# Sheet1.net
KiCad netlist of a schematic drawn in Altium Designer
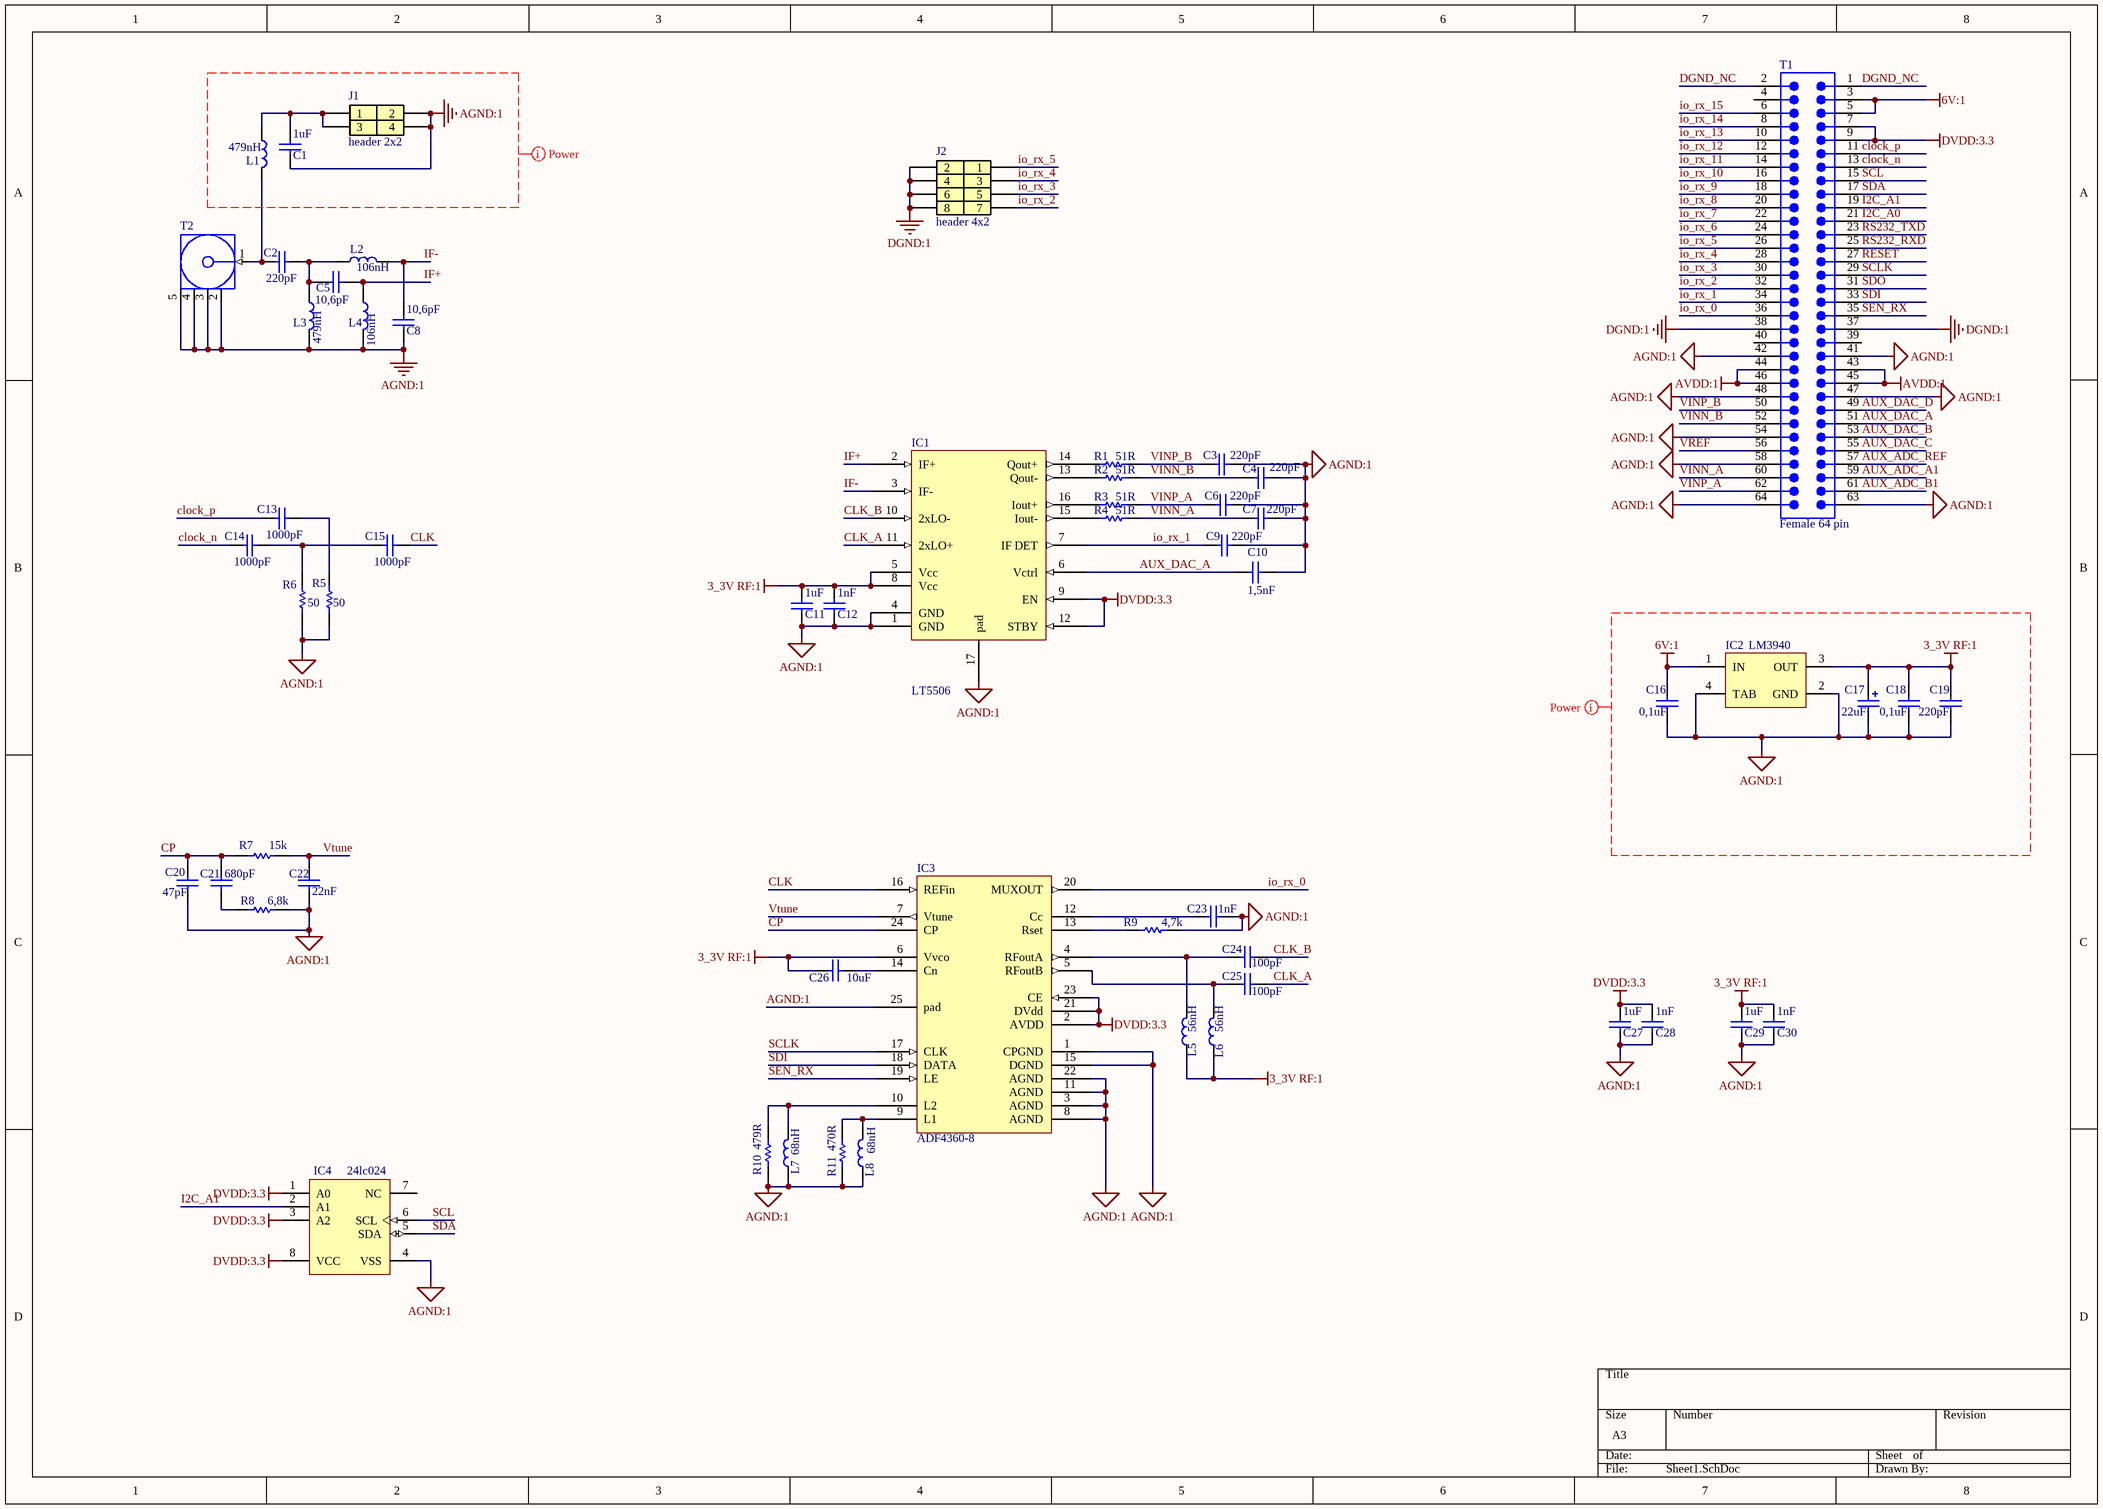
[diagram p0: Sheet1.SchDoc]

(export (version "E")
  (design (tool "Eeschema 10.0.6"))
  (components
    (comp (ref "C1") (value "1uF") (footprint "0805 cap") (libsource (lib "DB") (part "ceramic capacitor")))
    (comp (ref "C2") (value "220pF") (footprint "0805 cap") (libsource (lib "DB") (part "ceramic capacitor")))
    (comp (ref "C3") (value "220pF") (footprint "0805 cap") (libsource (lib "DB") (part "ceramic capacitor")))
    (comp (ref "C4") (value "220pF") (footprint "0805 cap") (libsource (lib "DB") (part "ceramic capacitor")))
    (comp (ref "C5")
      (value "10,6pF")
      (footprint "0805 cap")
      (libsource (lib "DB") (part "ceramic capacitor"))
    )
    (comp (ref "C6") (value "220pF") (footprint "0805 cap") (libsource (lib "DB") (part "ceramic capacitor")))
    (comp (ref "C7") (value "220pF") (footprint "0805 cap") (libsource (lib "DB") (part "ceramic capacitor")))
    (comp (ref "C8")
      (value "10,6pF")
      (footprint "0805 cap")
      (libsource (lib "DB") (part "ceramic capacitor"))
    )
    (comp (ref "C9") (value "220pF") (footprint "0805 cap") (libsource (lib "DB") (part "ceramic capacitor")))
    (comp (ref "C10")
      (value "1,5nF")
      (footprint "0805 cap")
      (libsource (lib "DB") (part "ceramic capacitor"))
    )
    (comp (ref "C11") (value "1uF") (footprint "0805 cap") (libsource (lib "DB") (part "ceramic capacitor")))
    (comp (ref "C12") (value "1nF") (footprint "0805 cap") (libsource (lib "DB") (part "ceramic capacitor")))
    (comp (ref "C13")
      (value "1000pF")
      (footprint "0805 cap")
      (libsource (lib "DB") (part "ceramic capacitor"))
    )
    (comp (ref "C14")
      (value "1000pF")
      (footprint "0805 cap")
      (libsource (lib "DB") (part "ceramic capacitor"))
    )
    (comp (ref "C15")
      (value "1000pF")
      (footprint "0805 cap")
      (libsource (lib "DB") (part "ceramic capacitor"))
    )
    (comp (ref "C16")
      (value "0,1uF")
      (footprint "0805 cap")
      (libsource (lib "DB") (part "ceramic capacitor"))
    )
    (comp (ref "C17")
      (value "22uF")
      (footprint "capacitor C")
      (libsource (lib "DB") (part "tantalum capacitor"))
    )
    (comp (ref "C18")
      (value "0,1uF")
      (footprint "0805 cap")
      (libsource (lib "DB") (part "ceramic capacitor"))
    )
    (comp (ref "C19")
      (value "220pF")
      (footprint "0805 cap")
      (libsource (lib "DB") (part "ceramic capacitor"))
    )
    (comp (ref "C20") (value "47pF") (footprint "0805 cap") (libsource (lib "DB") (part "ceramic capacitor")))
    (comp (ref "C21")
      (value "680pF")
      (footprint "0805 cap")
      (libsource (lib "DB") (part "ceramic capacitor"))
    )
    (comp (ref "C22") (value "22nF") (footprint "0805 cap") (libsource (lib "DB") (part "ceramic capacitor")))
    (comp (ref "C23") (value "1nF") (footprint "0805 cap") (libsource (lib "DB") (part "ceramic capacitor")))
    (comp (ref "C24")
      (value "100pF")
      (footprint "0805 cap")
      (libsource (lib "DB") (part "ceramic capacitor"))
    )
    (comp (ref "C25")
      (value "100pF")
      (footprint "0805 cap")
      (libsource (lib "DB") (part "ceramic capacitor"))
    )
    (comp (ref "C26") (value "10uF") (footprint "0805 cap") (libsource (lib "DB") (part "ceramic capacitor")))
    (comp (ref "C27") (value "1uF") (footprint "0805 cap") (libsource (lib "DB") (part "ceramic capacitor")))
    (comp (ref "C28") (value "1nF") (footprint "0805 cap") (libsource (lib "DB") (part "ceramic capacitor")))
    (comp (ref "C29") (value "1uF") (footprint "0805 cap") (libsource (lib "DB") (part "ceramic capacitor")))
    (comp (ref "C30") (value "1nF") (footprint "0805 cap") (libsource (lib "DB") (part "ceramic capacitor")))
    (comp (ref "IC1")
      (value "LT5506")
      (footprint "QFN65P400X400X80-16N")
      (description "40MHz to 500MHz  Quadrature Demodulator  with VGA")
      (libsource (lib "DB") (part "LT5506"))
    )
    (comp (ref "IC2") (value "LM3940") (footprint "TO-263") (libsource (lib "DB") (part "LM3940")))
    (comp (ref "IC3")
      (value "ADF4360-8")
      (footprint "DB:QFN50P408X408X100-24N")
      (description "Integrated Synthesizer and VCO")
      (libsource (lib "DB") (part "ADF4360-8"))
    )
    (comp (ref "IC4") (value "24lc024") (footprint "SOIC_SN8") (libsource (lib "DB") (part "24lc024")))
    (comp (ref "J1") (value "header 2x2") (footprint "pld 2x2") (libsource (lib "DB") (part "header 2x2")))
    (comp (ref "J2") (value "header 4x2") (footprint "H_4x2") (libsource (lib "DB") (part "header 4x2")))
    (comp (ref "L1") (value "479nH") (footprint "inductor 0805") (libsource (lib "DB") (part "inductor")))
    (comp (ref "L2") (value "106nH") (footprint "inductor 0805") (libsource (lib "") (part "inductor_1")))
    (comp (ref "L3") (value "479nH") (footprint "inductor 0805") (libsource (lib "DB") (part "inductor")))
    (comp (ref "L4") (value "106nH") (footprint "inductor 0805") (libsource (lib "DB") (part "inductor")))
    (comp (ref "L5") (value "56nH") (footprint "inductor 0805") (libsource (lib "DB") (part "inductor")))
    (comp (ref "L6") (value "56nH") (footprint "inductor 0805") (libsource (lib "DB") (part "inductor")))
    (comp (ref "L7") (value "68nH") (footprint "inductor 0805") (libsource (lib "DB") (part "inductor")))
    (comp (ref "L8") (value "68nH") (footprint "inductor 0805") (libsource (lib "DB") (part "inductor")))
    (comp (ref "R1") (value "51R") (footprint "0805 resistor") (libsource (lib "DB") (part "resistor")))
    (comp (ref "R2") (value "51R") (footprint "0805 resistor") (libsource (lib "DB") (part "resistor")))
    (comp (ref "R3") (value "51R") (footprint "0805 resistor") (libsource (lib "DB") (part "resistor")))
    (comp (ref "R4") (value "51R") (footprint "0805 resistor") (libsource (lib "DB") (part "resistor")))
    (comp (ref "R5") (value "50") (footprint "0805 resistor") (libsource (lib "DB") (part "resistor")))
    (comp (ref "R6") (value "50") (footprint "0805 resistor") (libsource (lib "DB") (part "resistor")))
    (comp (ref "R7") (value "15k") (footprint "0805 resistor") (libsource (lib "DB") (part "resistor")))
    (comp (ref "R8") (value "6,8k") (footprint "0805 resistor") (libsource (lib "DB") (part "resistor")))
    (comp (ref "R9") (value "4,7k") (footprint "0805 resistor") (libsource (lib "DB") (part "resistor")))
    (comp (ref "R10") (value "479R") (footprint "0805 resistor") (libsource (lib "DB") (part "resistor")))
    (comp (ref "R11") (value "470R") (footprint "0805 resistor") (libsource (lib "DB") (part "resistor")))
    (comp (ref "T1")
      (value "Female 64 pin")
      (footprint "64pin female Mezzanine")
      (libsource (lib "DB") (part "Female 64 pin"))
    )
    (comp (ref "T2") (value "mcx_connect") (footprint "mcx_ra") (libsource (lib "DB") (part "mcx_connect")))
  )
  (nets
    (net (code "1") (name "/AUX_ADC_A1") (class "Default")
      (node (ref "T1") (pin "59") (pinfunction "59_59") (pintype "passive"))
    )
    (net (code "2") (name "/AUX_ADC_B1") (class "Default")
      (node (ref "T1") (pin "61") (pinfunction "61_61") (pintype "passive"))
    )
    (net (code "3") (name "/AUX_ADC_REF") (class "Default")
      (node (ref "T1") (pin "57") (pinfunction "57_57") (pintype "passive"))
    )
    (net (code "4") (name "/AUX_DAC_A") (class "Default")
      (node (ref "C10") (pin "2") (pinfunction "2_2") (pintype "passive"))
      (node (ref "IC1") (pin "6") (pinfunction "Vctrl_6") (pintype "input"))
      (node (ref "T1") (pin "51") (pinfunction "51_51") (pintype "passive"))
    )
    (net (code "5") (name "/AUX_DAC_B") (class "Default")
      (node (ref "T1") (pin "53") (pinfunction "53_53") (pintype "passive"))
    )
    (net (code "6") (name "/AUX_DAC_C") (class "Default")
      (node (ref "T1") (pin "55") (pinfunction "55_55") (pintype "passive"))
    )
    (net (code "7") (name "/AUX_DAC_D") (class "Default")
      (node (ref "T1") (pin "49") (pinfunction "49_49") (pintype "passive"))
    )
    (net (code "8") (name "/CLK") (class "Default")
      (node (ref "C15") (pin "2") (pinfunction "2_2") (pintype "passive"))
      (node (ref "IC3") (pin "16") (pinfunction "REFin_16") (pintype "input"))
    )
    (net (code "9") (name "/CLK_A") (class "Default")
      (node (ref "C25") (pin "1") (pinfunction "1_1") (pintype "passive"))
      (node (ref "IC1") (pin "11") (pinfunction "2xLO+_11") (pintype "input"))
    )
    (net (code "10") (name "/CLK_B") (class "Default")
      (node (ref "C24") (pin "1") (pinfunction "1_1") (pintype "passive"))
      (node (ref "IC1") (pin "10") (pinfunction "2xLO-_10") (pintype "input"))
    )
    (net (code "11") (name "/CP") (class "Default")
      (node (ref "C20") (pin "2") (pinfunction "2_2") (pintype "passive"))
      (node (ref "C21") (pin "2") (pinfunction "2_2") (pintype "passive"))
      (node (ref "IC3") (pin "24") (pinfunction "CP_24") (pintype "passive"))
      (node (ref "R7") (pin "1") (pinfunction "1_1") (pintype "passive"))
    )
    (net (code "12") (name "/DGND_NC") (class "Default")
      (node (ref "T1") (pin "1") (pinfunction "1_1") (pintype "passive"))
      (node (ref "T1") (pin "2") (pinfunction "2_2") (pintype "passive"))
    )
    (net (code "13") (name "/I2C_A0") (class "Default")
      (node (ref "T1") (pin "21") (pinfunction "21_21") (pintype "passive"))
    )
    (net (code "14") (name "/I2C_A1") (class "Default")
      (node (ref "IC4") (pin "2") (pinfunction "A1_2") (pintype "passive"))
      (node (ref "T1") (pin "19") (pinfunction "19_19") (pintype "passive"))
    )
    (net (code "15") (name "/IF+") (class "Default")
      (node (ref "C5") (pin "2") (pinfunction "2_2") (pintype "passive"))
      (node (ref "IC1") (pin "2") (pinfunction "IF+_2") (pintype "input"))
      (node (ref "L4") (pin "1") (pinfunction "1_1") (pintype "passive"))
    )
    (net (code "16") (name "/IF-") (class "Default")
      (node (ref "C8") (pin "2") (pinfunction "2_2") (pintype "passive"))
      (node (ref "IC1") (pin "3") (pinfunction "IF-_3") (pintype "input"))
      (node (ref "L2") (pin "2") (pinfunction "2_2") (pintype "passive"))
    )
    (net (code "17") (name "/RESET") (class "Default")
      (node (ref "T1") (pin "27") (pinfunction "27_27") (pintype "passive"))
    )
    (net (code "18") (name "/RS232_RXD") (class "Default")
      (node (ref "T1") (pin "25") (pinfunction "25_25") (pintype "passive"))
    )
    (net (code "19") (name "/RS232_TXD") (class "Default")
      (node (ref "T1") (pin "23") (pinfunction "23_23") (pintype "passive"))
    )
    (net (code "20") (name "/SCL") (class "Default")
      (node (ref "IC4") (pin "6") (pinfunction "SCL_6") (pintype "input"))
      (node (ref "T1") (pin "15") (pinfunction "15_15") (pintype "passive"))
    )
    (net (code "21") (name "/SCLK") (class "Default")
      (node (ref "IC3") (pin "17") (pinfunction "CLK_17") (pintype "input"))
      (node (ref "T1") (pin "29") (pinfunction "29_29") (pintype "passive"))
    )
    (net (code "22") (name "/SDA") (class "Default")
      (node (ref "IC4") (pin "5") (pinfunction "SDA_5") (pintype "bidirectional"))
      (node (ref "T1") (pin "17") (pinfunction "17_17") (pintype "passive"))
    )
    (net (code "23") (name "/SDI") (class "Default")
      (node (ref "IC3") (pin "18") (pinfunction "DATA_18") (pintype "input"))
      (node (ref "T1") (pin "33") (pinfunction "33_33") (pintype "passive"))
    )
    (net (code "24") (name "/SDO") (class "Default")
      (node (ref "T1") (pin "31") (pinfunction "31_31") (pintype "passive"))
    )
    (net (code "25") (name "/SEN_RX") (class "Default")
      (node (ref "IC3") (pin "19") (pinfunction "LE_19") (pintype "input"))
      (node (ref "T1") (pin "35") (pinfunction "35_35") (pintype "passive"))
    )
    (net (code "26") (name "/VINN_A") (class "Default")
      (node (ref "C7") (pin "1") (pinfunction "1_1") (pintype "passive"))
      (node (ref "R4") (pin "2") (pinfunction "2_2") (pintype "passive"))
      (node (ref "T1") (pin "60") (pinfunction "60_60") (pintype "passive"))
    )
    (net (code "27") (name "/VINN_B") (class "Default")
      (node (ref "C4") (pin "1") (pinfunction "1_1") (pintype "passive"))
      (node (ref "R2") (pin "2") (pinfunction "2_2") (pintype "passive"))
      (node (ref "T1") (pin "52") (pinfunction "52_52") (pintype "passive"))
    )
    (net (code "28") (name "/VINP_A") (class "Default")
      (node (ref "C6") (pin "1") (pinfunction "1_1") (pintype "passive"))
      (node (ref "R3") (pin "2") (pinfunction "2_2") (pintype "passive"))
      (node (ref "T1") (pin "62") (pinfunction "62_62") (pintype "passive"))
    )
    (net (code "29") (name "/VINP_B") (class "Default")
      (node (ref "C3") (pin "1") (pinfunction "1_1") (pintype "passive"))
      (node (ref "R1") (pin "2") (pinfunction "2_2") (pintype "passive"))
      (node (ref "T1") (pin "50") (pinfunction "50_50") (pintype "passive"))
    )
    (net (code "30") (name "/VREF") (class "Default")
      (node (ref "T1") (pin "56") (pinfunction "56_56") (pintype "passive"))
    )
    (net (code "31") (name "/Vtune") (class "Default")
      (node (ref "C22") (pin "2") (pinfunction "2_2") (pintype "passive"))
      (node (ref "IC3") (pin "7") (pinfunction "Vtune_7") (pintype "output"))
      (node (ref "R7") (pin "2") (pinfunction "2_2") (pintype "passive"))
    )
    (net (code "32") (name "/clock_n") (class "Default")
      (node (ref "C14") (pin "1") (pinfunction "1_1") (pintype "passive"))
      (node (ref "T1") (pin "13") (pinfunction "13_13") (pintype "passive"))
    )
    (net (code "33") (name "/clock_p") (class "Default")
      (node (ref "C13") (pin "1") (pinfunction "1_1") (pintype "passive"))
      (node (ref "T1") (pin "11") (pinfunction "11_11") (pintype "passive"))
    )
    (net (code "34") (name "/io_rx_0") (class "Default")
      (node (ref "IC3") (pin "20") (pinfunction "MUXOUT_20") (pintype "output"))
      (node (ref "T1") (pin "36") (pinfunction "36_36") (pintype "passive"))
    )
    (net (code "35") (name "/io_rx_1") (class "Default")
      (node (ref "C9") (pin "1") (pinfunction "1_1") (pintype "passive"))
      (node (ref "IC1") (pin "7") (pinfunction "IF_DET_7") (pintype "output"))
      (node (ref "T1") (pin "34") (pinfunction "34_34") (pintype "passive"))
    )
    (net (code "36") (name "/io_rx_2") (class "Default")
      (node (ref "J2") (pin "7") (pinfunction "7_7") (pintype "passive"))
      (node (ref "T1") (pin "32") (pinfunction "32_32") (pintype "passive"))
    )
    (net (code "37") (name "/io_rx_3") (class "Default")
      (node (ref "J2") (pin "5") (pinfunction "5_5") (pintype "passive"))
      (node (ref "T1") (pin "30") (pinfunction "30_30") (pintype "passive"))
    )
    (net (code "38") (name "/io_rx_4") (class "Default")
      (node (ref "J2") (pin "3") (pinfunction "3_3") (pintype "passive"))
      (node (ref "T1") (pin "28") (pinfunction "28_28") (pintype "passive"))
    )
    (net (code "39") (name "/io_rx_5") (class "Default")
      (node (ref "J2") (pin "1") (pinfunction "1_1") (pintype "passive"))
      (node (ref "T1") (pin "26") (pinfunction "26_26") (pintype "passive"))
    )
    (net (code "40") (name "/io_rx_6") (class "Default")
      (node (ref "T1") (pin "24") (pinfunction "24_24") (pintype "passive"))
    )
    (net (code "41") (name "/io_rx_7") (class "Default")
      (node (ref "T1") (pin "22") (pinfunction "22_22") (pintype "passive"))
    )
    (net (code "42") (name "/io_rx_8") (class "Default")
      (node (ref "T1") (pin "20") (pinfunction "20_20") (pintype "passive"))
    )
    (net (code "43") (name "/io_rx_9") (class "Default")
      (node (ref "T1") (pin "18") (pinfunction "18_18") (pintype "passive"))
    )
    (net (code "44") (name "/io_rx_10") (class "Default")
      (node (ref "T1") (pin "16") (pinfunction "16_16") (pintype "passive"))
    )
    (net (code "45") (name "/io_rx_11") (class "Default")
      (node (ref "T1") (pin "14") (pinfunction "14_14") (pintype "passive"))
    )
    (net (code "46") (name "/io_rx_12") (class "Default")
      (node (ref "T1") (pin "12") (pinfunction "12_12") (pintype "passive"))
    )
    (net (code "47") (name "/io_rx_13") (class "Default")
      (node (ref "T1") (pin "10") (pinfunction "10_10") (pintype "passive"))
    )
    (net (code "48") (name "/io_rx_14") (class "Default")
      (node (ref "T1") (pin "8") (pinfunction "8_8") (pintype "passive"))
    )
    (net (code "49") (name "/io_rx_15") (class "Default")
      (node (ref "T1") (pin "6") (pinfunction "6_6") (pintype "passive"))
    )
    (net (code "50") (name "3_3V RF:1") (class "Default")
      (node (ref "C11") (pin "2") (pinfunction "2_2") (pintype "passive"))
      (node (ref "C12") (pin "2") (pinfunction "2_2") (pintype "passive"))
      (node (ref "C17") (pin "1") (pinfunction "1_1") (pintype "passive"))
      (node (ref "C18") (pin "2") (pinfunction "2_2") (pintype "passive"))
      (node (ref "C19") (pin "2") (pinfunction "2_2") (pintype "passive"))
      (node (ref "C26") (pin "1") (pinfunction "1_1") (pintype "passive"))
      (node (ref "C29") (pin "2") (pinfunction "2_2") (pintype "passive"))
      (node (ref "C30") (pin "2") (pinfunction "2_2") (pintype "passive"))
      (node (ref "IC1") (pin "5") (pinfunction "Vcc_5") (pintype "power_in"))
      (node (ref "IC1") (pin "8") (pinfunction "Vcc_8") (pintype "power_in"))
      (node (ref "IC2") (pin "3") (pinfunction "OUT_3") (pintype "power_in"))
      (node (ref "IC3") (pin "6") (pinfunction "Vvco_6") (pintype "power_in"))
      (node (ref "L5") (pin "1") (pinfunction "1_1") (pintype "passive"))
      (node (ref "L6") (pin "1") (pinfunction "1_1") (pintype "passive"))
    )
    (net (code "51") (name "6V:1") (class "Default")
      (node (ref "C16") (pin "1") (pinfunction "1_1") (pintype "passive"))
      (node (ref "IC2") (pin "1") (pinfunction "IN_1") (pintype "power_in"))
      (node (ref "T1") (pin "3") (pinfunction "3_3") (pintype "passive"))
      (node (ref "T1") (pin "5") (pinfunction "5_5") (pintype "passive"))
    )
    (net (code "52") (name "AGND:1") (class "Default")
      (node (ref "C1") (pin "1") (pinfunction "1_1") (pintype "passive"))
      (node (ref "C10") (pin "1") (pinfunction "1_1") (pintype "passive"))
      (node (ref "C11") (pin "1") (pinfunction "1_1") (pintype "passive"))
      (node (ref "C12") (pin "1") (pinfunction "1_1") (pintype "passive"))
      (node (ref "C16") (pin "2") (pinfunction "2_2") (pintype "passive"))
      (node (ref "C17") (pin "2") (pinfunction "2_2") (pintype "passive"))
      (node (ref "C18") (pin "1") (pinfunction "1_1") (pintype "passive"))
      (node (ref "C19") (pin "1") (pinfunction "1_1") (pintype "passive"))
      (node (ref "C20") (pin "1") (pinfunction "1_1") (pintype "passive"))
      (node (ref "C22") (pin "1") (pinfunction "1_1") (pintype "passive"))
      (node (ref "C23") (pin "1") (pinfunction "1_1") (pintype "passive"))
      (node (ref "C27") (pin "1") (pinfunction "1_1") (pintype "passive"))
      (node (ref "C28") (pin "1") (pinfunction "1_1") (pintype "passive"))
      (node (ref "C29") (pin "1") (pinfunction "1_1") (pintype "passive"))
      (node (ref "C3") (pin "2") (pinfunction "2_2") (pintype "passive"))
      (node (ref "C30") (pin "1") (pinfunction "1_1") (pintype "passive"))
      (node (ref "C4") (pin "2") (pinfunction "2_2") (pintype "passive"))
      (node (ref "C6") (pin "2") (pinfunction "2_2") (pintype "passive"))
      (node (ref "C7") (pin "2") (pinfunction "2_2") (pintype "passive"))
      (node (ref "C8") (pin "1") (pinfunction "1_1") (pintype "passive"))
      (node (ref "C9") (pin "2") (pinfunction "2_2") (pintype "passive"))
      (node (ref "IC1") (pin "1") (pinfunction "GND_1") (pintype "power_in"))
      (node (ref "IC1") (pin "17") (pinfunction "pad_17") (pintype "passive"))
      (node (ref "IC1") (pin "4") (pinfunction "GND_4") (pintype "power_in"))
      (node (ref "IC2") (pin "2") (pinfunction "GND_2") (pintype "power_in"))
      (node (ref "IC2") (pin "4") (pinfunction "TAB_4") (pintype "power_in"))
      (node (ref "IC3") (pin "1") (pinfunction "CPGND_1") (pintype "power_in"))
      (node (ref "IC3") (pin "11") (pinfunction "AGND_11") (pintype "power_in"))
      (node (ref "IC3") (pin "15") (pinfunction "DGND_15") (pintype "power_in"))
      (node (ref "IC3") (pin "22") (pinfunction "AGND_22") (pintype "power_in"))
      (node (ref "IC3") (pin "25") (pinfunction "pad_25") (pintype "passive"))
      (node (ref "IC3") (pin "3") (pinfunction "AGND_3") (pintype "power_in"))
      (node (ref "IC3") (pin "8") (pinfunction "AGND_8") (pintype "power_in"))
      (node (ref "IC4") (pin "4") (pinfunction "VSS_4") (pintype "power_in"))
      (node (ref "J1") (pin "2") (pinfunction "2_2") (pintype "passive"))
      (node (ref "J1") (pin "4") (pinfunction "4_4") (pintype "passive"))
      (node (ref "L3") (pin "2") (pinfunction "2_2") (pintype "passive"))
      (node (ref "L4") (pin "2") (pinfunction "2_2") (pintype "passive"))
      (node (ref "L7") (pin "1") (pinfunction "1_1") (pintype "passive"))
      (node (ref "L8") (pin "1") (pinfunction "1_1") (pintype "passive"))
      (node (ref "R10") (pin "1") (pinfunction "1_1") (pintype "passive"))
      (node (ref "R11") (pin "1") (pinfunction "1_1") (pintype "passive"))
      (node (ref "R5") (pin "1") (pinfunction "1_1") (pintype "passive"))
      (node (ref "R6") (pin "1") (pinfunction "1_1") (pintype "passive"))
      (node (ref "R8") (pin "2") (pinfunction "2_2") (pintype "passive"))
      (node (ref "R9") (pin "2") (pinfunction "2_2") (pintype "passive"))
      (node (ref "T1") (pin "41") (pinfunction "41_41") (pintype "passive"))
      (node (ref "T1") (pin "42") (pinfunction "42_42") (pintype "passive"))
      (node (ref "T1") (pin "47") (pinfunction "47_47") (pintype "passive"))
      (node (ref "T1") (pin "48") (pinfunction "48_48") (pintype "passive"))
      (node (ref "T1") (pin "54") (pinfunction "54_54") (pintype "passive"))
      (node (ref "T1") (pin "58") (pinfunction "58_58") (pintype "passive"))
      (node (ref "T1") (pin "63") (pinfunction "63_63") (pintype "passive"))
      (node (ref "T1") (pin "64") (pinfunction "64_64") (pintype "passive"))
      (node (ref "T2") (pin "2") (pinfunction "GND_2") (pintype "power_in"))
      (node (ref "T2") (pin "3") (pinfunction "GND_3") (pintype "power_in"))
      (node (ref "T2") (pin "4") (pinfunction "GND_4") (pintype "power_in"))
      (node (ref "T2") (pin "5") (pinfunction "GND_5") (pintype "power_in"))
    )
    (net (code "53") (name "AVDD:1") (class "Default")
      (node (ref "T1") (pin "43") (pinfunction "43_43") (pintype "passive"))
      (node (ref "T1") (pin "44") (pinfunction "44_44") (pintype "passive"))
      (node (ref "T1") (pin "45") (pinfunction "45_45") (pintype "passive"))
      (node (ref "T1") (pin "46") (pinfunction "46_46") (pintype "passive"))
    )
    (net (code "54") (name "DGND:1") (class "Default")
      (node (ref "J2") (pin "2") (pinfunction "2_2") (pintype "passive"))
      (node (ref "J2") (pin "4") (pinfunction "4_4") (pintype "passive"))
      (node (ref "J2") (pin "6") (pinfunction "6_6") (pintype "passive"))
      (node (ref "J2") (pin "8") (pinfunction "8_8") (pintype "passive"))
      (node (ref "T1") (pin "37") (pinfunction "37_37") (pintype "passive"))
      (node (ref "T1") (pin "38") (pinfunction "38_38") (pintype "passive"))
    )
    (net (code "55") (name "DVDD:3.3") (class "Default")
      (node (ref "C27") (pin "2") (pinfunction "2_2") (pintype "passive"))
      (node (ref "C28") (pin "2") (pinfunction "2_2") (pintype "passive"))
      (node (ref "IC1") (pin "12") (pinfunction "STBY_12") (pintype "input"))
      (node (ref "IC1") (pin "9") (pinfunction "EN_9") (pintype "input"))
      (node (ref "IC3") (pin "2") (pinfunction "AVDD_2") (pintype "power_in"))
      (node (ref "IC3") (pin "21") (pinfunction "DVdd_21") (pintype "power_in"))
      (node (ref "IC3") (pin "23") (pinfunction "CE_23") (pintype "input"))
      (node (ref "IC4") (pin "1") (pinfunction "A0_1") (pintype "passive"))
      (node (ref "IC4") (pin "3") (pinfunction "A2_3") (pintype "passive"))
      (node (ref "IC4") (pin "8") (pinfunction "VCC_8") (pintype "power_in"))
      (node (ref "T1") (pin "7") (pinfunction "7_7") (pintype "passive"))
      (node (ref "T1") (pin "9") (pinfunction "9_9") (pintype "passive"))
    )
    (net (code "56") (name "Net-(C1-Pad2)") (class "Default")
      (node (ref "C1") (pin "2") (pinfunction "2_2") (pintype "passive"))
      (node (ref "J1") (pin "1") (pinfunction "1_1") (pintype "passive"))
      (node (ref "J1") (pin "3") (pinfunction "3_3") (pintype "passive"))
      (node (ref "L1") (pin "1") (pinfunction "1_1") (pintype "passive"))
    )
    (net (code "57") (name "Net-(C2-Pad2)") (class "Default")
      (node (ref "C2") (pin "2") (pinfunction "2_2") (pintype "passive"))
      (node (ref "C5") (pin "1") (pinfunction "1_1") (pintype "passive"))
      (node (ref "L2") (pin "1") (pinfunction "1_1") (pintype "passive"))
      (node (ref "L3") (pin "1") (pinfunction "1_1") (pintype "passive"))
    )
    (net (code "58") (name "Net-(C13-Pad2)") (class "Default")
      (node (ref "C13") (pin "2") (pinfunction "2_2") (pintype "passive"))
      (node (ref "R5") (pin "2") (pinfunction "2_2") (pintype "passive"))
    )
    (net (code "59") (name "Net-(C14-Pad2)") (class "Default")
      (node (ref "C14") (pin "2") (pinfunction "2_2") (pintype "passive"))
      (node (ref "C15") (pin "1") (pinfunction "1_1") (pintype "passive"))
      (node (ref "R6") (pin "2") (pinfunction "2_2") (pintype "passive"))
    )
    (net (code "60") (name "Net-(C21-Pad1)") (class "Default")
      (node (ref "C21") (pin "1") (pinfunction "1_1") (pintype "passive"))
      (node (ref "R8") (pin "1") (pinfunction "1_1") (pintype "passive"))
    )
    (net (code "61") (name "Net-(IC1-Iout+)") (class "Default")
      (node (ref "IC1") (pin "16") (pinfunction "Iout+_16") (pintype "output"))
      (node (ref "R3") (pin "1") (pinfunction "1_1") (pintype "passive"))
    )
    (net (code "62") (name "Net-(IC1-Iout-)") (class "Default")
      (node (ref "IC1") (pin "15") (pinfunction "Iout-_15") (pintype "output"))
      (node (ref "R4") (pin "1") (pinfunction "1_1") (pintype "passive"))
    )
    (net (code "63") (name "Net-(IC1-Qout+)") (class "Default")
      (node (ref "IC1") (pin "14") (pinfunction "Qout+_14") (pintype "output"))
      (node (ref "R1") (pin "1") (pinfunction "1_1") (pintype "passive"))
    )
    (net (code "64") (name "Net-(IC1-Qout-)") (class "Default")
      (node (ref "IC1") (pin "13") (pinfunction "Qout-_13") (pintype "output"))
      (node (ref "R2") (pin "1") (pinfunction "1_1") (pintype "passive"))
    )
    (net (code "65") (name "Net-(IC3-Cc)") (class "Default")
      (node (ref "C23") (pin "2") (pinfunction "2_2") (pintype "passive"))
      (node (ref "IC3") (pin "12") (pinfunction "Cc_12") (pintype "passive"))
    )
    (net (code "66") (name "Net-(IC3-Cn)") (class "Default")
      (node (ref "C26") (pin "2") (pinfunction "2_2") (pintype "passive"))
      (node (ref "IC3") (pin "14") (pinfunction "Cn_14") (pintype "passive"))
    )
    (net (code "67") (name "Net-(IC3-L1)") (class "Default")
      (node (ref "IC3") (pin "9") (pinfunction "L1_9") (pintype "passive"))
      (node (ref "L8") (pin "2") (pinfunction "2_2") (pintype "passive"))
      (node (ref "R11") (pin "2") (pinfunction "2_2") (pintype "passive"))
    )
    (net (code "68") (name "Net-(IC3-L2)") (class "Default")
      (node (ref "IC3") (pin "10") (pinfunction "L2_10") (pintype "passive"))
      (node (ref "L7") (pin "2") (pinfunction "2_2") (pintype "passive"))
      (node (ref "R10") (pin "2") (pinfunction "2_2") (pintype "passive"))
    )
    (net (code "69") (name "Net-(IC3-RFoutA)") (class "Default")
      (node (ref "C24") (pin "2") (pinfunction "2_2") (pintype "passive"))
      (node (ref "IC3") (pin "4") (pinfunction "RFoutA_4") (pintype "output"))
      (node (ref "L5") (pin "2") (pinfunction "2_2") (pintype "passive"))
    )
    (net (code "70") (name "Net-(IC3-RFoutB)") (class "Default")
      (node (ref "C25") (pin "2") (pinfunction "2_2") (pintype "passive"))
      (node (ref "IC3") (pin "5") (pinfunction "RFoutB_5") (pintype "output"))
      (node (ref "L6") (pin "2") (pinfunction "2_2") (pintype "passive"))
    )
    (net (code "71") (name "Net-(IC3-Rset)") (class "Default")
      (node (ref "IC3") (pin "13") (pinfunction "Rset_13") (pintype "passive"))
      (node (ref "R9") (pin "1") (pinfunction "1_1") (pintype "passive"))
    )
    (net (code "72") (name "Net-(T2-Signal)") (class "Default")
      (node (ref "C2") (pin "1") (pinfunction "1_1") (pintype "passive"))
      (node (ref "L1") (pin "2") (pinfunction "2_2") (pintype "passive"))
      (node (ref "T2") (pin "1") (pinfunction "Signal_1") (pintype "input"))
    )
    (net (code "73") (name "unconnected-(IC4-NC-Pad7)") (class "Default")
      (node (ref "IC4") (pin "7") (pinfunction "NC_7") (pintype "passive"))
    )
    (net (code "74") (name "unconnected-(T1-Pad4)") (class "Default")
      (node (ref "T1") (pin "4") (pinfunction "4_4") (pintype "passive"))
    )
    (net (code "75") (name "unconnected-(T1-Pad39)") (class "Default")
      (node (ref "T1") (pin "39") (pinfunction "39_39") (pintype "passive"))
    )
    (net (code "76") (name "unconnected-(T1-Pad40)") (class "Default")
      (node (ref "T1") (pin "40") (pinfunction "40_40") (pintype "passive"))
    )
  )
)
